# POWER.net
KiCad netlist of a schematic drawn in Altium Designer
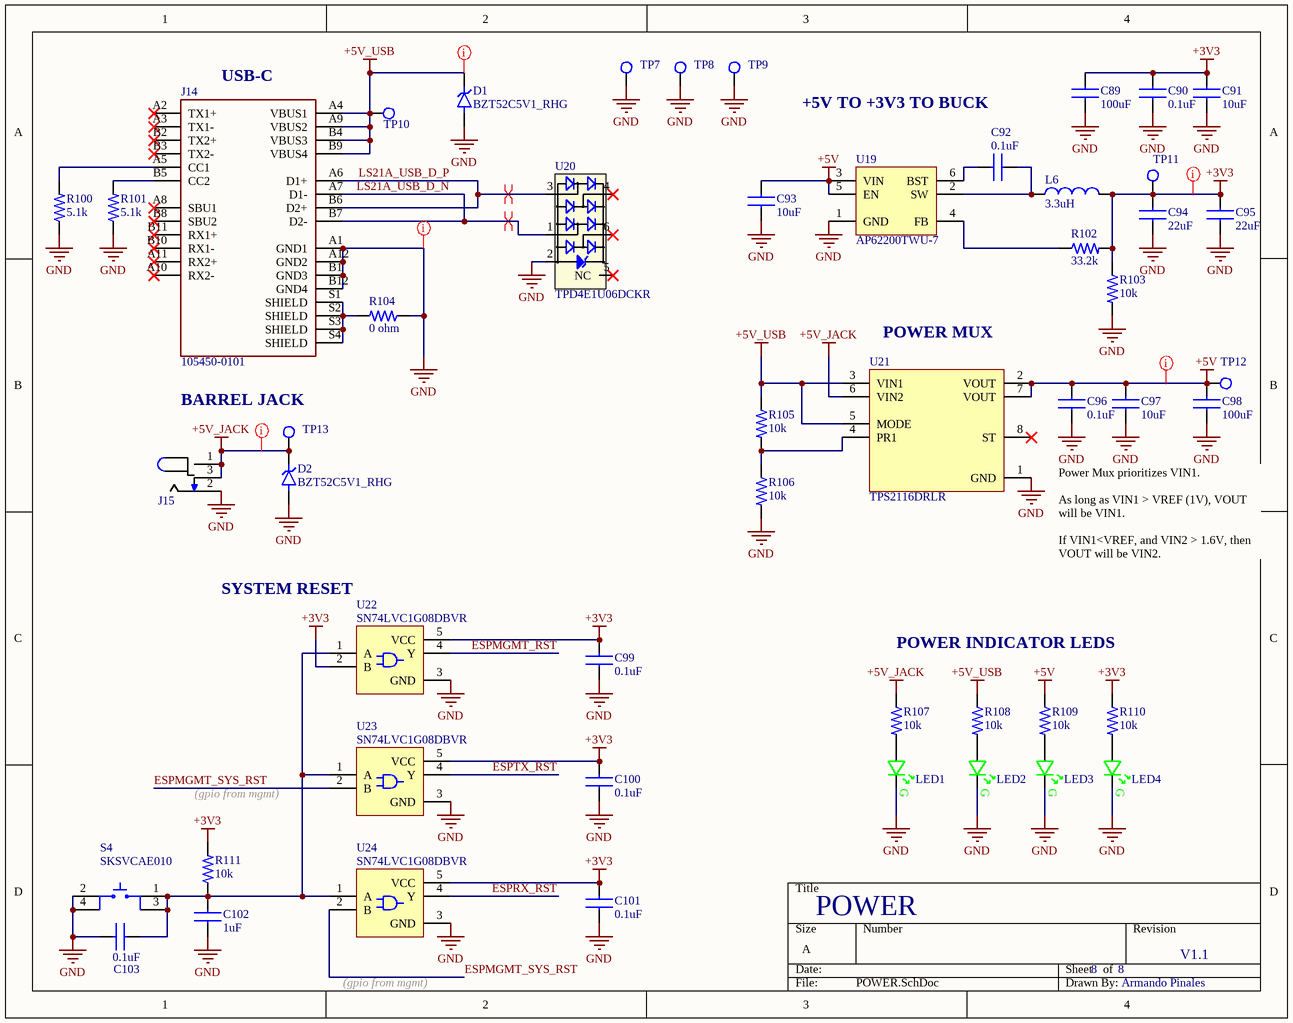
[diagram p0: POWER.SchDoc]

(export (version "E")
  (design (tool "Eeschema 10.0.6"))
  (components
    (comp (ref "C89")
      (value "100uF")
      (footprint "CAP_0805")
      (description "0805 100 uF 6.3 V ±20% Tolerance X5R Multilayer Ceramic Chip Capacitor")
      (fields
        (field (name "MANUFACTURER") "Murata")
        (field (name "MANUFACTURER PART NUMBER") "GRM21BR60J107ME15L")
      )
      (libsource (lib "LotusSound") (part "CAP_GRM21BR60J107ME15L"))
    )
    (comp (ref "C90")
      (value "0.1uF")
      (footprint "CAP_0402")
      (description "Cap Ceramic 0.1uF 16V X7R 10% SMD 0402 125C Paper T/R")
      (fields
        (field (name "MANUFACTURER") "Murata")
        (field (name "MANUFACTURER PART NUMBER") "GCM155R71C104KA55J")
      )
      (libsource (lib "LotusSound") (part "CAP_GCM155R71C104KA55J"))
    )
    (comp (ref "C91")
      (value "10uF")
      (footprint "CAP_0402")
      (description "Cap Ceramic 10uF 6.3V X5R 20% SMD 0402 85°C Paper T/R")
      (fields
        (field (name "MANUFACTURER") "Samsung")
        (field (name "MANUFACTURER PART NUMBER") "CL05A106MQ5NUNC")
      )
      (libsource (lib "LotusSound") (part "CAP_CL05A106MQ5NUNC"))
    )
    (comp (ref "C92")
      (value "0.1uF")
      (footprint "CAP_0402")
      (description "Cap Ceramic 0.1uF 16V X7R 10% SMD 0402 125C Paper T/R")
      (fields
        (field (name "MANUFACTURER") "Murata")
        (field (name "MANUFACTURER PART NUMBER") "GCM155R71C104KA55J")
      )
      (libsource (lib "LotusSound") (part "CAP_GCM155R71C104KA55J"))
    )
    (comp (ref "C93")
      (value "10uF")
      (footprint "CAP_0402")
      (description "Cap Ceramic 10uF 6.3V X5R 20% SMD 0402 85°C Paper T/R")
      (fields
        (field (name "MANUFACTURER") "Samsung")
        (field (name "MANUFACTURER PART NUMBER") "CL05A106MQ5NUNC")
      )
      (libsource (lib "LotusSound") (part "CAP_CL05A106MQ5NUNC"))
    )
    (comp (ref "C94")
      (value "22uF")
      (footprint "CAP_0402")
      (description "General Up to 85C Reflow soldering")
      (fields
        (field (name "MANUFACTURER") "Murata")
        (field (name "MANUFACTURER PART NUMBER") "GRM158R61A226ME15D")
      )
      (libsource (lib "LotusSound") (part "CAP_GRM158R61A226ME15D"))
    )
    (comp (ref "C95")
      (value "22uF")
      (footprint "CAP_0402")
      (description "General Up to 85C Reflow soldering")
      (fields
        (field (name "MANUFACTURER") "Murata")
        (field (name "MANUFACTURER PART NUMBER") "GRM158R61A226ME15D")
      )
      (libsource (lib "LotusSound") (part "CAP_GRM158R61A226ME15D"))
    )
    (comp (ref "C96")
      (value "0.1uF")
      (footprint "CAP_0402")
      (description "Cap Ceramic 0.1uF 16V X7R 10% SMD 0402 125C Paper T/R")
      (fields
        (field (name "MANUFACTURER") "Murata")
        (field (name "MANUFACTURER PART NUMBER") "GCM155R71C104KA55J")
      )
      (libsource (lib "LotusSound") (part "CAP_GCM155R71C104KA55J"))
    )
    (comp (ref "C97")
      (value "10uF")
      (footprint "CAP_0402")
      (description "Cap Ceramic 10uF 6.3V X5R 20% SMD 0402 85°C Paper T/R")
      (fields
        (field (name "MANUFACTURER") "Samsung")
        (field (name "MANUFACTURER PART NUMBER") "CL05A106MQ5NUNC")
      )
      (libsource (lib "LotusSound") (part "CAP_CL05A106MQ5NUNC"))
    )
    (comp (ref "C98")
      (value "100uF")
      (footprint "CAP_0805")
      (description "0805 100 uF 6.3 V ±20% Tolerance X5R Multilayer Ceramic Chip Capacitor")
      (fields
        (field (name "MANUFACTURER") "Murata")
        (field (name "MANUFACTURER PART NUMBER") "GRM21BR60J107ME15L")
      )
      (libsource (lib "LotusSound") (part "CAP_GRM21BR60J107ME15L"))
    )
    (comp (ref "C99")
      (value "0.1uF")
      (footprint "CAP_0402")
      (description "Cap Ceramic 0.1uF 16V X7R 10% SMD 0402 125C Paper T/R")
      (fields
        (field (name "MANUFACTURER") "Murata")
        (field (name "MANUFACTURER PART NUMBER") "GCM155R71C104KA55J")
      )
      (libsource (lib "LotusSound") (part "CAP_GCM155R71C104KA55J"))
    )
    (comp (ref "C100")
      (value "0.1uF")
      (footprint "CAP_0402")
      (description "Cap Ceramic 0.1uF 16V X7R 10% SMD 0402 125C Paper T/R")
      (fields
        (field (name "MANUFACTURER") "Murata")
        (field (name "MANUFACTURER PART NUMBER") "GCM155R71C104KA55J")
      )
      (libsource (lib "LotusSound") (part "CAP_GCM155R71C104KA55J"))
    )
    (comp (ref "C101")
      (value "0.1uF")
      (footprint "CAP_0402")
      (description "Cap Ceramic 0.1uF 16V X7R 10% SMD 0402 125C Paper T/R")
      (fields
        (field (name "MANUFACTURER") "Murata")
        (field (name "MANUFACTURER PART NUMBER") "GCM155R71C104KA55J")
      )
      (libsource (lib "LotusSound") (part "CAP_GCM155R71C104KA55J"))
    )
    (comp (ref "C102")
      (value "1uF")
      (footprint "CAP_0402")
      (description "Cap Ceramic 1uF 25V X5R 10% SMD 0402 85°C Cardboard T/R")
      (fields
        (field (name "MANUFACTURER") "Samsung")
        (field (name "MANUFACTURER PART NUMBER") "CL05A105KA5NQNC")
      )
      (libsource (lib "LotusSound") (part "CAP_CL05A105KA5NQNC"))
    )
    (comp (ref "C103")
      (value "0.1uF")
      (footprint "CAP_0402")
      (description "Cap Ceramic 0.1uF 16V X7R 10% SMD 0402 125C Paper T/R")
      (fields
        (field (name "MANUFACTURER") "Murata")
        (field (name "MANUFACTURER PART NUMBER") "GCM155R71C104KA55J")
      )
      (libsource (lib "LotusSound") (part "CAP_GCM155R71C104KA55J"))
    )
    (comp (ref "D1")
      (value "BZT52C5V1_RHG")
      (footprint "D_BZT52C5V1_RHG")
      (description "Vz=5.1V 4.8V~5.4V Izt=5mA")
      (fields (field (name "MP") "BZT52C5V1 RHG") (field (name "MF") "Taiwan Semiconductor"))
      (libsource (lib "LotusSound") (part "D_BZT52C5V1_RHG"))
    )
    (comp (ref "D2")
      (value "BZT52C5V1_RHG")
      (footprint "D_BZT52C5V1_RHG")
      (description "Vz=5.1V 4.8V~5.4V Izt=5mA")
      (fields (field (name "MP") "BZT52C5V1 RHG") (field (name "MF") "Taiwan Semiconductor"))
      (libsource (lib "LotusSound") (part "D_BZT52C5V1_RHG"))
    )
    (comp (ref "J14")
      (value "105450-0101")
      (footprint "CONN_105450-0101")
      (fields (field (name "MF") "Molex"))
      (libsource (lib "LotusSound") (part "CONN_105450-0101"))
    )
    (comp (ref "J15")
      (value "Power Jack")
      (footprint "CONN_DC-005-20A")
      (description "Power Barrel Connector Jack 2.10mm ID (0.083\"), 5.50mm OD (0.217\") Through Hole, Right Angle")
      (fields (field (name "DIGIKEY PART") "CP-102A-ND") (field (name "LCSC PART#") "C136744"))
      (libsource (lib "LotusSound") (part "CONN_DC-005-20A"))
    )
    (comp (ref "L6")
      (value "3.3uH")
      (footprint "L_IHLP2020CZER3R3M01")
      (description "Inductor Power Shielded Wirewound 3.3uH 20% 100KHz Powdered Iron 5A 54.7mOhm DCR 2020 T/R")
      (fields
        (field (name "MANUFACTURER") "Vishay Dale")
        (field (name "MANUFACTURER PART NUMBER") "IHLP2020CZER3R3M01")
      )
      (libsource (lib "LotusSound") (part "L_IHLP2020CZER3R3M01"))
    )
    (comp (ref "LED1")
      (value "LED_SM0402GC")
      (footprint "LED_FP-SM0402GC-MFG")
      (description "LED Uni-Color Green 575nm 2-Pin Chip 0402(1006Metric) T/R")
      (fields (field (name "MANUFACTURER") "Bivar") (field (name "MANUFACTURER PART NUMBER") "SM0402GC"))
      (libsource (lib "LotusSound") (part "LED_SM0402GC"))
    )
    (comp (ref "LED2")
      (value "LED_SM0402GC")
      (footprint "LED_FP-SM0402GC-MFG")
      (description "LED Uni-Color Green 575nm 2-Pin Chip 0402(1006Metric) T/R")
      (fields (field (name "MANUFACTURER") "Bivar") (field (name "MANUFACTURER PART NUMBER") "SM0402GC"))
      (libsource (lib "LotusSound") (part "LED_SM0402GC"))
    )
    (comp (ref "LED3")
      (value "LED_SM0402GC")
      (footprint "LED_FP-SM0402GC-MFG")
      (description "LED Uni-Color Green 575nm 2-Pin Chip 0402(1006Metric) T/R")
      (fields (field (name "MANUFACTURER") "Bivar") (field (name "MANUFACTURER PART NUMBER") "SM0402GC"))
      (libsource (lib "LotusSound") (part "LED_SM0402GC"))
    )
    (comp (ref "LED4")
      (value "LED_SM0402GC")
      (footprint "LED_FP-SM0402GC-MFG")
      (description "LED Uni-Color Green 575nm 2-Pin Chip 0402(1006Metric) T/R")
      (fields (field (name "MANUFACTURER") "Bivar") (field (name "MANUFACTURER PART NUMBER") "SM0402GC"))
      (libsource (lib "LotusSound") (part "LED_SM0402GC"))
    )
    (comp (ref "R100")
      (value "5.1k")
      (footprint "RES_0402")
      (description "Res Thick Film 0402 5.1K Ohm 1% 0.063W ±100ppm/°C Molded SMD Paper T/R")
      (fields
        (field (name "MANUFACTURER") "Stackpole Electronics")
        (field (name "MANUFACTURER PART NUMBER") "RMCF0402FT5K10")
      )
      (libsource (lib "LotusSound") (part "RES_RMCF0402FT5K10"))
    )
    (comp (ref "R101")
      (value "5.1k")
      (footprint "RES_0402")
      (description "Res Thick Film 0402 5.1K Ohm 1% 0.063W ±100ppm/°C Molded SMD Paper T/R")
      (fields
        (field (name "MANUFACTURER") "Stackpole Electronics")
        (field (name "MANUFACTURER PART NUMBER") "RMCF0402FT5K10")
      )
      (libsource (lib "LotusSound") (part "RES_RMCF0402FT5K10"))
    )
    (comp (ref "R102")
      (value "33.2k")
      (footprint "RES_0402")
      (description "Res General Purpose Thick Film 0402 33.2K Ohm 1% 1/16W ±100ppm/°C Molded SMD Paper T/R")
      (fields
        (field (name "MANUFACTURER") "Yageo")
        (field (name "MANUFACTURER PART NUMBER") "RC0402FR-0733K2L")
      )
      (libsource (lib "LotusSound") (part "RES_RC0402FR-0733K2L"))
    )
    (comp (ref "R103")
      (value "10k")
      (footprint "RES_0402")
      (description "RES SMD 10K OHM 1% 1/16W 0402")
      (fields
        (field (name "MANUFACTURER") "Yageo")
        (field (name "MANUFACTURER PART NUMBER") "AC0402FR-0710KL")
      )
      (libsource (lib "LotusSound") (part "RES_AC0402FR-0710KL"))
    )
    (comp (ref "R104")
      (value "0 ohm")
      (footprint "RES_0402")
      (description "RES SMD 0 OHM JUMPER 1/16W 0402")
      (fields
        (field (name "MANUFACTURER") "Yageo")
        (field (name "MANUFACTURER PART NUMBER") "RC0402JR-070RL")
      )
      (libsource (lib "LotusSound") (part "RES_RC0402JR-070RL"))
    )
    (comp (ref "R105")
      (value "10k")
      (footprint "RES_0402")
      (description "RES SMD 10K OHM 1% 1/16W 0402")
      (fields
        (field (name "MANUFACTURER") "Yageo")
        (field (name "MANUFACTURER PART NUMBER") "AC0402FR-0710KL")
      )
      (libsource (lib "LotusSound") (part "RES_AC0402FR-0710KL"))
    )
    (comp (ref "R106")
      (value "10k")
      (footprint "RES_0402")
      (description "RES SMD 10K OHM 1% 1/16W 0402")
      (fields
        (field (name "MANUFACTURER") "Yageo")
        (field (name "MANUFACTURER PART NUMBER") "AC0402FR-0710KL")
      )
      (libsource (lib "LotusSound") (part "RES_AC0402FR-0710KL"))
    )
    (comp (ref "R107")
      (value "10k")
      (footprint "RES_0402")
      (description "RES SMD 10K OHM 1% 1/16W 0402")
      (fields
        (field (name "MANUFACTURER") "Yageo")
        (field (name "MANUFACTURER PART NUMBER") "AC0402FR-0710KL")
      )
      (libsource (lib "LotusSound") (part "RES_AC0402FR-0710KL"))
    )
    (comp (ref "R108")
      (value "10k")
      (footprint "RES_0402")
      (description "RES SMD 10K OHM 1% 1/16W 0402")
      (fields
        (field (name "MANUFACTURER") "Yageo")
        (field (name "MANUFACTURER PART NUMBER") "AC0402FR-0710KL")
      )
      (libsource (lib "LotusSound") (part "RES_AC0402FR-0710KL"))
    )
    (comp (ref "R109")
      (value "10k")
      (footprint "RES_0402")
      (description "RES SMD 10K OHM 1% 1/16W 0402")
      (fields
        (field (name "MANUFACTURER") "Yageo")
        (field (name "MANUFACTURER PART NUMBER") "AC0402FR-0710KL")
      )
      (libsource (lib "LotusSound") (part "RES_AC0402FR-0710KL"))
    )
    (comp (ref "R110")
      (value "10k")
      (footprint "RES_0402")
      (description "RES SMD 10K OHM 1% 1/16W 0402")
      (fields
        (field (name "MANUFACTURER") "Yageo")
        (field (name "MANUFACTURER PART NUMBER") "AC0402FR-0710KL")
      )
      (libsource (lib "LotusSound") (part "RES_AC0402FR-0710KL"))
    )
    (comp (ref "R111")
      (value "10k")
      (footprint "RES_0402")
      (description "RES SMD 10K OHM 1% 1/16W 0402")
      (fields
        (field (name "MANUFACTURER") "Yageo")
        (field (name "MANUFACTURER PART NUMBER") "AC0402FR-0710KL")
      )
      (libsource (lib "LotusSound") (part "RES_AC0402FR-0710KL"))
    )
    (comp (ref "S4")
      (value "SKSVCAE010")
      (footprint "SW_SKSVCAE010")
      (description "2.8x1.9mm Compact Type with Projection Surface Mount SKSV Series Tact Switch")
      (fields (field (name "MANUFACTURER") "Alps Electric"))
      (libsource (lib "LotusSound") (part "SW_SKSVCAE010"))
    )
    (comp (ref "TP7")
      (value "Test Point 1MM")
      (footprint "TP_PAD-1MM")
      (libsource (lib "LotusSound") (part "TP_PAD-1MM"))
    )
    (comp (ref "TP8")
      (value "Test Point 1MM")
      (footprint "TP_PAD-1MM")
      (libsource (lib "LotusSound") (part "TP_PAD-1MM"))
    )
    (comp (ref "TP9")
      (value "Test Point 1MM")
      (footprint "TP_PAD-1MM")
      (libsource (lib "LotusSound") (part "TP_PAD-1MM"))
    )
    (comp (ref "TP10")
      (value "Test Point 1MM")
      (footprint "TP_PAD-1MM")
      (libsource (lib "LotusSound") (part "TP_PAD-1MM"))
    )
    (comp (ref "TP11")
      (value "Test Point 1MM")
      (footprint "TP_PAD-1MM")
      (libsource (lib "LotusSound") (part "TP_PAD-1MM"))
    )
    (comp (ref "TP12")
      (value "Test Point 1MM")
      (footprint "TP_PAD-1MM")
      (libsource (lib "LotusSound") (part "TP_PAD-1MM"))
    )
    (comp (ref "TP13")
      (value "Test Point 1MM")
      (footprint "TP_PAD-1MM")
      (libsource (lib "LotusSound") (part "TP_PAD-1MM"))
    )
    (comp (ref "U19")
      (value "AP62200TWU-7")
      (footprint "IC_AP62200TWU-7")
      (description "4.2V to 18V Input, 2A Low Iq Synchronous Buck Converter, Pfm/pwm")
      (fields (field (name "MANUFACTURER") "Diodes"))
      (libsource (lib "LotusSound") (part "IC_AP62200TWU-7"))
    )
    (comp (ref "U20")
      (value "TPD4E1U06DCKR")
      (footprint "IC_TPD4E1U06DCKR")
      (description "TVS DIODE 5.5VWM 15VC SC70-6")
      (fields (field (name "MANUFACTURER") "Texas Instruments"))
      (libsource (lib "LotusSound") (part "IC_TPD4E1U06DCKR"))
    )
    (comp (ref "U21")
      (value "TPS2116DRLR")
      (footprint "IC_TPS2116")
      (description "1.6-V to 5.5-V, 40-mΩ, 2.5-A, low-IQ, priority power multiplexer 8-SOT-5X3 -40 to 125")
      (fields (field (name "MF") "Texas Instruments"))
      (libsource (lib "LotusSound") (part "IC_TPS2116DRLR"))
    )
    (comp (ref "U22")
      (value "SN74LVC1G08DBVR")
      (footprint "IC_SN74LVC1G08DBVR")
      (description "AND Gate IC 1 Channel  SOT-23-5")
      (fields (field (name "MF") "Texas Instruments"))
      (libsource (lib "LotusSound") (part "IC_SN74LVC1G08DBVR"))
    )
    (comp (ref "U23")
      (value "SN74LVC1G08DBVR")
      (footprint "IC_SN74LVC1G08DBVR")
      (description "AND Gate IC 1 Channel  SOT-23-5")
      (fields (field (name "MF") "Texas Instruments"))
      (libsource (lib "LotusSound") (part "IC_SN74LVC1G08DBVR"))
    )
    (comp (ref "U24")
      (value "SN74LVC1G08DBVR")
      (footprint "IC_SN74LVC1G08DBVR")
      (description "AND Gate IC 1 Channel  SOT-23-5")
      (fields (field (name "MF") "Texas Instruments"))
      (libsource (lib "LotusSound") (part "IC_SN74LVC1G08DBVR"))
    )
  )
  (nets
    (net (code "1") (name "+3V3") (class "Default")
      (node (ref "C100") (pin "2") (pinfunction "2_2") (pintype "passive"))
      (node (ref "C101") (pin "2") (pinfunction "2_2") (pintype "passive"))
      (node (ref "C89") (pin "2") (pinfunction "2_2") (pintype "passive"))
      (node (ref "C90") (pin "2") (pinfunction "2_2") (pintype "passive"))
      (node (ref "C91") (pin "2") (pinfunction "2_2") (pintype "passive"))
      (node (ref "C94") (pin "2") (pinfunction "2_2") (pintype "passive"))
      (node (ref "C95") (pin "2") (pinfunction "2_2") (pintype "passive"))
      (node (ref "C99") (pin "2") (pinfunction "2_2") (pintype "passive"))
      (node (ref "L6") (pin "2") (pinfunction "2_2") (pintype "passive"))
      (node (ref "R102") (pin "2") (pinfunction "2_2") (pintype "passive"))
      (node (ref "R103") (pin "1") (pinfunction "1_1") (pintype "passive"))
      (node (ref "R110") (pin "1") (pinfunction "1_1") (pintype "passive"))
      (node (ref "R111") (pin "2") (pinfunction "2_2") (pintype "passive"))
      (node (ref "TP11") (pin "1") (pinfunction "1_1") (pintype "passive"))
      (node (ref "U22") (pin "2") (pinfunction "B_2") (pintype "passive"))
      (node (ref "U22") (pin "5") (pinfunction "VCC_5") (pintype "power_in"))
      (node (ref "U23") (pin "5") (pinfunction "VCC_5") (pintype "power_in"))
      (node (ref "U24") (pin "5") (pinfunction "VCC_5") (pintype "power_in"))
    )
    (net (code "2") (name "+5V") (class "Default")
      (node (ref "C93") (pin "2") (pinfunction "2_2") (pintype "passive"))
      (node (ref "C96") (pin "2") (pinfunction "2_2") (pintype "passive"))
      (node (ref "C97") (pin "2") (pinfunction "2_2") (pintype "passive"))
      (node (ref "C98") (pin "2") (pinfunction "2_2") (pintype "passive"))
      (node (ref "R109") (pin "1") (pinfunction "1_1") (pintype "passive"))
      (node (ref "TP12") (pin "1") (pinfunction "1_1") (pintype "passive"))
      (node (ref "U19") (pin "3") (pinfunction "VIN_3") (pintype "passive"))
      (node (ref "U19") (pin "5") (pinfunction "EN_5") (pintype "passive"))
      (node (ref "U21") (pin "2") (pinfunction "VOUT_2") (pintype "passive"))
      (node (ref "U21") (pin "7") (pinfunction "VOUT_7") (pintype "passive"))
    )
    (net (code "3") (name "+5V_JACK") (class "Default")
      (node (ref "D2") (pin "C") (pinfunction "K_C") (pintype "passive"))
      (node (ref "J15") (pin "1") (pinfunction "1_1") (pintype "power_in"))
      (node (ref "J15") (pin "3") (pinfunction "3_3") (pintype "power_in"))
      (node (ref "R107") (pin "1") (pinfunction "1_1") (pintype "passive"))
      (node (ref "TP13") (pin "1") (pinfunction "1_1") (pintype "passive"))
      (node (ref "U21") (pin "6") (pinfunction "VIN2_6") (pintype "passive"))
    )
    (net (code "4") (name "+5V_USB") (class "Default")
      (node (ref "D1") (pin "C") (pinfunction "K_C") (pintype "passive"))
      (node (ref "J14") (pin "A4") (pinfunction "VBUS1_A4") (pintype "passive"))
      (node (ref "J14") (pin "A9") (pinfunction "VBUS2_A9") (pintype "passive"))
      (node (ref "J14") (pin "B4") (pinfunction "VBUS3_B4") (pintype "passive"))
      (node (ref "J14") (pin "B9") (pinfunction "VBUS4_B9") (pintype "passive"))
      (node (ref "R105") (pin "1") (pinfunction "1_1") (pintype "passive"))
      (node (ref "R108") (pin "1") (pinfunction "1_1") (pintype "passive"))
      (node (ref "TP10") (pin "1") (pinfunction "1_1") (pintype "passive"))
      (node (ref "U21") (pin "3") (pinfunction "VIN1_3") (pintype "passive"))
      (node (ref "U21") (pin "5") (pinfunction "MODE_5") (pintype "passive"))
    )
    (net (code "5") (name "/ESPMGMT_RST") (class "Default")
      (node (ref "U22") (pin "4") (pinfunction "Y_4") (pintype "passive"))
    )
    (net (code "6") (name "/ESPMGMT_SYS_RST") (class "Default")
      (node (ref "U23") (pin "2") (pinfunction "B_2") (pintype "passive"))
      (node (ref "U24") (pin "2") (pinfunction "B_2") (pintype "passive"))
    )
    (net (code "7") (name "/ESPRX_RST") (class "Default")
      (node (ref "U24") (pin "4") (pinfunction "Y_4") (pintype "passive"))
    )
    (net (code "8") (name "/ESPTX_RST") (class "Default")
      (node (ref "U23") (pin "4") (pinfunction "Y_4") (pintype "passive"))
    )
    (net (code "9") (name "/LS21A_USB_D_N") (class "Default")
      (node (ref "J14") (pin "A7") (pinfunction "D1-_A7") (pintype "passive"))
      (node (ref "J14") (pin "B7") (pinfunction "D2-_B7") (pintype "passive"))
      (node (ref "U20") (pin "1") (pinfunction "D+_1") (pintype "passive"))
    )
    (net (code "10") (name "/LS21A_USB_D_P") (class "Default")
      (node (ref "J14") (pin "A6") (pinfunction "D1+_A6") (pintype "passive"))
      (node (ref "J14") (pin "B6") (pinfunction "D2+_B6") (pintype "passive"))
      (node (ref "U20") (pin "3") (pinfunction "D+_3") (pintype "passive"))
    )
    (net (code "11") (name "GND") (class "Default")
      (node (ref "C100") (pin "1") (pinfunction "1_1") (pintype "passive"))
      (node (ref "C101") (pin "1") (pinfunction "1_1") (pintype "passive"))
      (node (ref "C102") (pin "1") (pinfunction "1_1") (pintype "passive"))
      (node (ref "C103") (pin "1") (pinfunction "1_1") (pintype "passive"))
      (node (ref "C89") (pin "1") (pinfunction "1_1") (pintype "passive"))
      (node (ref "C90") (pin "1") (pinfunction "1_1") (pintype "passive"))
      (node (ref "C91") (pin "1") (pinfunction "1_1") (pintype "passive"))
      (node (ref "C93") (pin "1") (pinfunction "1_1") (pintype "passive"))
      (node (ref "C94") (pin "1") (pinfunction "1_1") (pintype "passive"))
      (node (ref "C95") (pin "1") (pinfunction "1_1") (pintype "passive"))
      (node (ref "C96") (pin "1") (pinfunction "1_1") (pintype "passive"))
      (node (ref "C97") (pin "1") (pinfunction "1_1") (pintype "passive"))
      (node (ref "C98") (pin "1") (pinfunction "1_1") (pintype "passive"))
      (node (ref "C99") (pin "1") (pinfunction "1_1") (pintype "passive"))
      (node (ref "D1") (pin "A") (pinfunction "A_A") (pintype "passive"))
      (node (ref "D2") (pin "A") (pinfunction "A_A") (pintype "passive"))
      (node (ref "J14") (pin "A1") (pinfunction "GND1_A1") (pintype "passive"))
      (node (ref "J14") (pin "A12") (pinfunction "GND2_A12") (pintype "passive"))
      (node (ref "J14") (pin "B1") (pinfunction "GND3_B1") (pintype "passive"))
      (node (ref "J14") (pin "B12") (pinfunction "GND4_B12") (pintype "passive"))
      (node (ref "J15") (pin "2") (pinfunction "2_2") (pintype "power_in"))
      (node (ref "LED1") (pin "2") (pinfunction "2_2") (pintype "passive"))
      (node (ref "LED2") (pin "2") (pinfunction "2_2") (pintype "passive"))
      (node (ref "LED3") (pin "2") (pinfunction "2_2") (pintype "passive"))
      (node (ref "LED4") (pin "2") (pinfunction "2_2") (pintype "passive"))
      (node (ref "R100") (pin "1") (pinfunction "1_1") (pintype "passive"))
      (node (ref "R101") (pin "1") (pinfunction "1_1") (pintype "passive"))
      (node (ref "R103") (pin "2") (pinfunction "2_2") (pintype "passive"))
      (node (ref "R104") (pin "1") (pinfunction "1_1") (pintype "passive"))
      (node (ref "R106") (pin "2") (pinfunction "2_2") (pintype "passive"))
      (node (ref "S4") (pin "2") (pinfunction "2_2") (pintype "passive"))
      (node (ref "S4") (pin "4") (pinfunction "4_4") (pintype "passive"))
      (node (ref "TP7") (pin "1") (pinfunction "1_1") (pintype "passive"))
      (node (ref "TP8") (pin "1") (pinfunction "1_1") (pintype "passive"))
      (node (ref "TP9") (pin "1") (pinfunction "1_1") (pintype "passive"))
      (node (ref "U19") (pin "1") (pinfunction "GND_1") (pintype "passive"))
      (node (ref "U20") (pin "2") (pinfunction "GND_2") (pintype "passive"))
      (node (ref "U21") (pin "1") (pinfunction "GND_1") (pintype "passive"))
      (node (ref "U22") (pin "3") (pinfunction "GND_3") (pintype "power_in"))
      (node (ref "U23") (pin "3") (pinfunction "GND_3") (pintype "power_in"))
      (node (ref "U24") (pin "3") (pinfunction "GND_3") (pintype "power_in"))
    )
    (net (code "12") (name "Net-(J14-CC1)") (class "Default")
      (node (ref "J14") (pin "A5") (pinfunction "CC1_A5") (pintype "passive"))
      (node (ref "R100") (pin "2") (pinfunction "2_2") (pintype "passive"))
    )
    (net (code "13") (name "Net-(J14-CC2)") (class "Default")
      (node (ref "J14") (pin "B5") (pinfunction "CC2_B5") (pintype "passive"))
      (node (ref "R101") (pin "2") (pinfunction "2_2") (pintype "passive"))
    )
    (net (code "14") (name "Net-(J14-SHIELD-PadS1)") (class "Default")
      (node (ref "J14") (pin "S1") (pinfunction "SHIELD_S1") (pintype "passive"))
      (node (ref "J14") (pin "S2") (pinfunction "SHIELD_S2") (pintype "passive"))
      (node (ref "J14") (pin "S3") (pinfunction "SHIELD_S3") (pintype "passive"))
      (node (ref "J14") (pin "S4") (pinfunction "SHIELD_S4") (pintype "passive"))
      (node (ref "R104") (pin "2") (pinfunction "2_2") (pintype "passive"))
    )
    (net (code "15") (name "Net-(LED1-Pad1)") (class "Default")
      (node (ref "LED1") (pin "1") (pinfunction "1_1") (pintype "passive"))
      (node (ref "R107") (pin "2") (pinfunction "2_2") (pintype "passive"))
    )
    (net (code "16") (name "Net-(LED2-Pad1)") (class "Default")
      (node (ref "LED2") (pin "1") (pinfunction "1_1") (pintype "passive"))
      (node (ref "R108") (pin "2") (pinfunction "2_2") (pintype "passive"))
    )
    (net (code "17") (name "Net-(LED3-Pad1)") (class "Default")
      (node (ref "LED3") (pin "1") (pinfunction "1_1") (pintype "passive"))
      (node (ref "R109") (pin "2") (pinfunction "2_2") (pintype "passive"))
    )
    (net (code "18") (name "Net-(LED4-Pad1)") (class "Default")
      (node (ref "LED4") (pin "1") (pinfunction "1_1") (pintype "passive"))
      (node (ref "R110") (pin "2") (pinfunction "2_2") (pintype "passive"))
    )
    (net (code "19") (name "Net-(U19-BST)") (class "Default")
      (node (ref "C92") (pin "2") (pinfunction "2_2") (pintype "passive"))
      (node (ref "U19") (pin "6") (pinfunction "BST_6") (pintype "passive"))
    )
    (net (code "20") (name "Net-(U19-FB)") (class "Default")
      (node (ref "R102") (pin "1") (pinfunction "1_1") (pintype "passive"))
      (node (ref "U19") (pin "4") (pinfunction "FB_4") (pintype "passive"))
    )
    (net (code "21") (name "Net-(U19-SW)") (class "Default")
      (node (ref "C92") (pin "1") (pinfunction "1_1") (pintype "passive"))
      (node (ref "L6") (pin "1") (pinfunction "1_1") (pintype "passive"))
      (node (ref "U19") (pin "2") (pinfunction "SW_2") (pintype "passive"))
    )
    (net (code "22") (name "Net-(U21-PR1)") (class "Default")
      (node (ref "R105") (pin "2") (pinfunction "2_2") (pintype "passive"))
      (node (ref "R106") (pin "1") (pinfunction "1_1") (pintype "passive"))
      (node (ref "U21") (pin "4") (pinfunction "PR1_4") (pintype "passive"))
    )
    (net (code "23") (name "Net-(U22-A)") (class "Default")
      (node (ref "C102") (pin "2") (pinfunction "2_2") (pintype "passive"))
      (node (ref "C103") (pin "2") (pinfunction "2_2") (pintype "passive"))
      (node (ref "R111") (pin "1") (pinfunction "1_1") (pintype "passive"))
      (node (ref "S4") (pin "1") (pinfunction "1_1") (pintype "passive"))
      (node (ref "S4") (pin "3") (pinfunction "3_3") (pintype "passive"))
      (node (ref "U22") (pin "1") (pinfunction "A_1") (pintype "passive"))
      (node (ref "U23") (pin "1") (pinfunction "A_1") (pintype "passive"))
      (node (ref "U24") (pin "1") (pinfunction "A_1") (pintype "passive"))
    )
    (net (code "24") (name "unconnected-(J14-RX1+-PadB11)") (class "Default")
      (node (ref "J14") (pin "B11") (pinfunction "RX1+_B11") (pintype "passive+no_connect"))
    )
    (net (code "25") (name "unconnected-(J14-RX1--PadB10)") (class "Default")
      (node (ref "J14") (pin "B10") (pinfunction "RX1-_B10") (pintype "passive+no_connect"))
    )
    (net (code "26") (name "unconnected-(J14-RX2+-PadA11)") (class "Default")
      (node (ref "J14") (pin "A11") (pinfunction "RX2+_A11") (pintype "passive+no_connect"))
    )
    (net (code "27") (name "unconnected-(J14-RX2--PadA10)") (class "Default")
      (node (ref "J14") (pin "A10") (pinfunction "RX2-_A10") (pintype "passive+no_connect"))
    )
    (net (code "28") (name "unconnected-(J14-SBU1-PadA8)") (class "Default")
      (node (ref "J14") (pin "A8") (pinfunction "SBU1_A8") (pintype "passive+no_connect"))
    )
    (net (code "29") (name "unconnected-(J14-SBU2-PadB8)") (class "Default")
      (node (ref "J14") (pin "B8") (pinfunction "SBU2_B8") (pintype "passive+no_connect"))
    )
    (net (code "30") (name "unconnected-(J14-TX1+-PadA2)") (class "Default")
      (node (ref "J14") (pin "A2") (pinfunction "TX1+_A2") (pintype "passive+no_connect"))
    )
    (net (code "31") (name "unconnected-(J14-TX1--PadA3)") (class "Default")
      (node (ref "J14") (pin "A3") (pinfunction "TX1-_A3") (pintype "passive+no_connect"))
    )
    (net (code "32") (name "unconnected-(J14-TX2+-PadB2)") (class "Default")
      (node (ref "J14") (pin "B2") (pinfunction "TX2+_B2") (pintype "passive+no_connect"))
    )
    (net (code "33") (name "unconnected-(J14-TX2--PadB3)") (class "Default")
      (node (ref "J14") (pin "B3") (pinfunction "TX2-_B3") (pintype "passive+no_connect"))
    )
    (net (code "34") (name "unconnected-(U20-D--Pad4)") (class "Default")
      (node (ref "U20") (pin "4") (pinfunction "D-_4") (pintype "passive+no_connect"))
    )
    (net (code "35") (name "unconnected-(U20-D--Pad6)") (class "Default")
      (node (ref "U20") (pin "6") (pinfunction "D-_6") (pintype "passive+no_connect"))
    )
    (net (code "36") (name "unconnected-(U20-NC-Pad5)") (class "Default")
      (node (ref "U20") (pin "5") (pinfunction "NC_5") (pintype "passive+no_connect"))
    )
    (net (code "37") (name "unconnected-(U21-ST-Pad8)") (class "Default")
      (node (ref "U21") (pin "8") (pinfunction "ST_8") (pintype "passive+no_connect"))
    )
  )
)
